# Rahul_Gupta_Breakout_Board.net
KiCad netlist of a schematic drawn in EAGLE
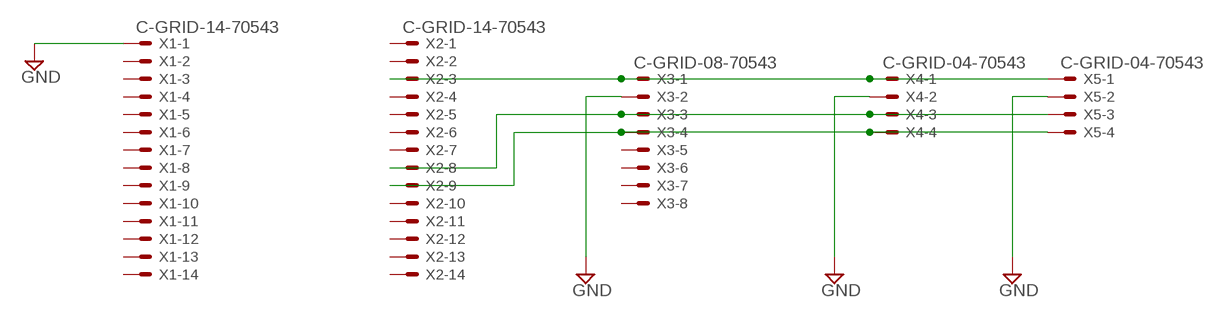
[diagram p0: schematic, sheet 1]

(export (version "E")
  (design (tool "Eeschema 10.0.6"))
  (components
    (comp (ref "X1")
      (value "C-GRID-14-70543")
      (footprint "eagle-import:70543-14")
      (fields (field (name "MF") "MOLEX"))
      (libsource (lib "eagle-import") (part "C-GRID-14-70543"))
    )
    (comp (ref "X2")
      (value "C-GRID-14-70543")
      (footprint "eagle-import:70543-14")
      (fields (field (name "MF") "MOLEX"))
      (libsource (lib "eagle-import") (part "C-GRID-14-70543"))
    )
    (comp (ref "X3")
      (value "C-GRID-08-70543")
      (footprint "eagle-import:70543-08")
      (fields (field (name "MF") "MOLEX"))
      (libsource (lib "eagle-import") (part "C-GRID-08-70543"))
    )
    (comp (ref "X4")
      (value "C-GRID-04-70543")
      (footprint "eagle-import:70543-04")
      (fields (field (name "MF") "MOLEX"))
      (libsource (lib "eagle-import") (part "C-GRID-04-70543"))
    )
    (comp (ref "X5")
      (value "C-GRID-04-70543")
      (footprint "eagle-import:70543-04")
      (fields (field (name "MF") "MOLEX"))
      (libsource (lib "eagle-import") (part "C-GRID-04-70543"))
    )
  )
  (nets
    (net (code "1") (name "GND") (class "Default")
      (node (ref "X1") (pin "1") (pinfunction "S_1") (pintype "passive"))
      (node (ref "X3") (pin "2") (pinfunction "S_2") (pintype "passive"))
      (node (ref "X4") (pin "2") (pinfunction "S_2") (pintype "passive"))
      (node (ref "X5") (pin "2") (pinfunction "S_2") (pintype "passive"))
    )
    (net (code "2") (name "Net-(X2H-S)") (class "Default")
      (node (ref "X2") (pin "3") (pinfunction "S_3") (pintype "passive"))
      (node (ref "X3") (pin "1") (pinfunction "S_1") (pintype "passive"))
      (node (ref "X4") (pin "1") (pinfunction "S_1") (pintype "passive"))
      (node (ref "X5") (pin "1") (pinfunction "S_1") (pintype "passive"))
    )
    (net (code "3") (name "Net-(X2M-S)") (class "Default")
      (node (ref "X2") (pin "8") (pinfunction "S_8") (pintype "passive"))
      (node (ref "X3") (pin "3") (pinfunction "S_3") (pintype "passive"))
      (node (ref "X4") (pin "3") (pinfunction "S_3") (pintype "passive"))
      (node (ref "X5") (pin "3") (pinfunction "S_3") (pintype "passive"))
    )
    (net (code "4") (name "Net-(X2N-S)") (class "Default")
      (node (ref "X2") (pin "9") (pinfunction "S_9") (pintype "passive"))
      (node (ref "X3") (pin "4") (pinfunction "S_4") (pintype "passive"))
      (node (ref "X4") (pin "4") (pinfunction "S_4") (pintype "passive"))
      (node (ref "X5") (pin "4") (pinfunction "S_4") (pintype "passive"))
    )
    (net (code "5") (name "unconnected-(X1B-S-Pad10)") (class "Default")
      (node (ref "X1") (pin "10") (pinfunction "S_10") (pintype "passive"))
    )
    (net (code "6") (name "unconnected-(X1C-S-Pad11)") (class "Default")
      (node (ref "X1") (pin "11") (pinfunction "S_11") (pintype "passive"))
    )
    (net (code "7") (name "unconnected-(X1D-S-Pad12)") (class "Default")
      (node (ref "X1") (pin "12") (pinfunction "S_12") (pintype "passive"))
    )
    (net (code "8") (name "unconnected-(X1E-S-Pad13)") (class "Default")
      (node (ref "X1") (pin "13") (pinfunction "S_13") (pintype "passive"))
    )
    (net (code "9") (name "unconnected-(X1F-S-Pad14)") (class "Default")
      (node (ref "X1") (pin "14") (pinfunction "S_14") (pintype "passive"))
    )
    (net (code "10") (name "unconnected-(X1G-S-Pad2)") (class "Default")
      (node (ref "X1") (pin "2") (pinfunction "S_2") (pintype "passive"))
    )
    (net (code "11") (name "unconnected-(X1H-S-Pad3)") (class "Default")
      (node (ref "X1") (pin "3") (pinfunction "S_3") (pintype "passive"))
    )
    (net (code "12") (name "unconnected-(X1I-S-Pad4)") (class "Default")
      (node (ref "X1") (pin "4") (pinfunction "S_4") (pintype "passive"))
    )
    (net (code "13") (name "unconnected-(X1J-S-Pad5)") (class "Default")
      (node (ref "X1") (pin "5") (pinfunction "S_5") (pintype "passive"))
    )
    (net (code "14") (name "unconnected-(X1K-S-Pad6)") (class "Default")
      (node (ref "X1") (pin "6") (pinfunction "S_6") (pintype "passive"))
    )
    (net (code "15") (name "unconnected-(X1L-S-Pad7)") (class "Default")
      (node (ref "X1") (pin "7") (pinfunction "S_7") (pintype "passive"))
    )
    (net (code "16") (name "unconnected-(X1M-S-Pad8)") (class "Default")
      (node (ref "X1") (pin "8") (pinfunction "S_8") (pintype "passive"))
    )
    (net (code "17") (name "unconnected-(X1N-S-Pad9)") (class "Default")
      (node (ref "X1") (pin "9") (pinfunction "S_9") (pintype "passive"))
    )
    (net (code "18") (name "unconnected-(X2A-S-Pad1)") (class "Default")
      (node (ref "X2") (pin "1") (pinfunction "S_1") (pintype "passive"))
    )
    (net (code "19") (name "unconnected-(X2B-S-Pad10)") (class "Default")
      (node (ref "X2") (pin "10") (pinfunction "S_10") (pintype "passive"))
    )
    (net (code "20") (name "unconnected-(X2C-S-Pad11)") (class "Default")
      (node (ref "X2") (pin "11") (pinfunction "S_11") (pintype "passive"))
    )
    (net (code "21") (name "unconnected-(X2D-S-Pad12)") (class "Default")
      (node (ref "X2") (pin "12") (pinfunction "S_12") (pintype "passive"))
    )
    (net (code "22") (name "unconnected-(X2E-S-Pad13)") (class "Default")
      (node (ref "X2") (pin "13") (pinfunction "S_13") (pintype "passive"))
    )
    (net (code "23") (name "unconnected-(X2F-S-Pad14)") (class "Default")
      (node (ref "X2") (pin "14") (pinfunction "S_14") (pintype "passive"))
    )
    (net (code "24") (name "unconnected-(X2G-S-Pad2)") (class "Default")
      (node (ref "X2") (pin "2") (pinfunction "S_2") (pintype "passive"))
    )
    (net (code "25") (name "unconnected-(X2I-S-Pad4)") (class "Default")
      (node (ref "X2") (pin "4") (pinfunction "S_4") (pintype "passive"))
    )
    (net (code "26") (name "unconnected-(X2J-S-Pad5)") (class "Default")
      (node (ref "X2") (pin "5") (pinfunction "S_5") (pintype "passive"))
    )
    (net (code "27") (name "unconnected-(X2K-S-Pad6)") (class "Default")
      (node (ref "X2") (pin "6") (pinfunction "S_6") (pintype "passive"))
    )
    (net (code "28") (name "unconnected-(X2L-S-Pad7)") (class "Default")
      (node (ref "X2") (pin "7") (pinfunction "S_7") (pintype "passive"))
    )
    (net (code "29") (name "unconnected-(X3E-S-Pad5)") (class "Default")
      (node (ref "X3") (pin "5") (pinfunction "S_5") (pintype "passive"))
    )
    (net (code "30") (name "unconnected-(X3F-S-Pad6)") (class "Default")
      (node (ref "X3") (pin "6") (pinfunction "S_6") (pintype "passive"))
    )
    (net (code "31") (name "unconnected-(X3G-S-Pad7)") (class "Default")
      (node (ref "X3") (pin "7") (pinfunction "S_7") (pintype "passive"))
    )
    (net (code "32") (name "unconnected-(X3H-S-Pad8)") (class "Default")
      (node (ref "X3") (pin "8") (pinfunction "S_8") (pintype "passive"))
    )
  )
)
